# schematic_D_Amplifier_1.net
KiCad netlist of a schematic drawn in EAGLE
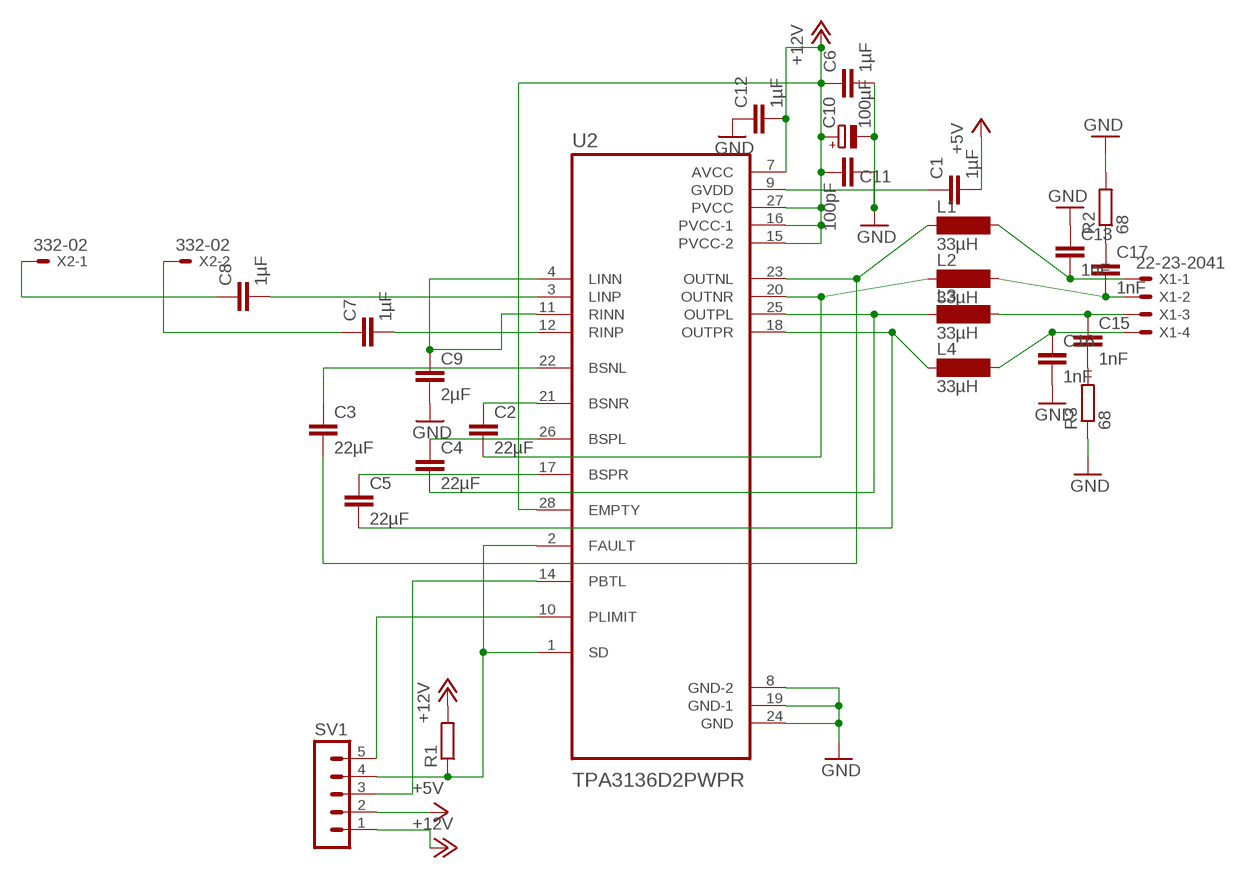
[diagram p0: schematic, sheet 1]

(export (version "E")
  (design (tool "Eeschema 10.0.6"))
  (components
    (comp (ref "C1")
      (value "1µF")
      (footprint "eagle-import:C025-025X050")
      (libsource (lib "eagle-import") (part "C-EU025-025X050"))
    )
    (comp (ref "C2")
      (value "22µF")
      (footprint "eagle-import:C025-025X050")
      (libsource (lib "eagle-import") (part "C-EU025-025X050"))
    )
    (comp (ref "C3")
      (value "22µF")
      (footprint "eagle-import:C025-025X050")
      (libsource (lib "eagle-import") (part "C-EU025-025X050"))
    )
    (comp (ref "C4")
      (value "22µF")
      (footprint "eagle-import:C025-025X050")
      (libsource (lib "eagle-import") (part "C-EU025-025X050"))
    )
    (comp (ref "C5")
      (value "22µF")
      (footprint "eagle-import:C025-025X050")
      (libsource (lib "eagle-import") (part "C-EU025-025X050"))
    )
    (comp (ref "C6")
      (value "1µF")
      (footprint "eagle-import:C025-025X050")
      (libsource (lib "eagle-import") (part "C-EU025-025X050"))
    )
    (comp (ref "C7")
      (value "1µF")
      (footprint "eagle-import:C025-025X050")
      (libsource (lib "eagle-import") (part "C-EU025-025X050"))
    )
    (comp (ref "C8")
      (value "1µF")
      (footprint "eagle-import:C025-025X050")
      (libsource (lib "eagle-import") (part "C-EU025-025X050"))
    )
    (comp (ref "C9")
      (value "2µF")
      (footprint "eagle-import:C025-025X050")
      (libsource (lib "eagle-import") (part "C-EU025-025X050"))
    )
    (comp (ref "C10")
      (value "100µF")
      (footprint "eagle-import:140CLH-1010")
      (libsource (lib "eagle-import") (part "CPOL-EU140CLH-1010"))
    )
    (comp (ref "C11")
      (value "100pF")
      (footprint "eagle-import:C025-025X050")
      (libsource (lib "eagle-import") (part "C-EU025-025X050"))
    )
    (comp (ref "C12")
      (value "1µF")
      (footprint "eagle-import:C025-025X050")
      (libsource (lib "eagle-import") (part "C-EU025-025X050"))
    )
    (comp (ref "C13")
      (value "1nF")
      (footprint "eagle-import:C025-025X050")
      (libsource (lib "eagle-import") (part "C-EU025-025X050"))
    )
    (comp (ref "C15")
      (value "1nF")
      (footprint "eagle-import:C025-025X050")
      (libsource (lib "eagle-import") (part "C-EU025-025X050"))
    )
    (comp (ref "C16")
      (value "1nF")
      (footprint "eagle-import:C025-025X050")
      (libsource (lib "eagle-import") (part "C-EU025-025X050"))
    )
    (comp (ref "C17")
      (value "1nF")
      (footprint "eagle-import:C025-025X050")
      (libsource (lib "eagle-import") (part "C-EU025-025X050"))
    )
    (comp (ref "L1")
      (value "33µH")
      (footprint "eagle-import:SD12-680")
      (fields (field (name "MF") "BUSSMANN") (field (name "MPN") "SD12-680"))
      (libsource (lib "eagle-import") (part "SD12-680"))
    )
    (comp (ref "L2")
      (value "33µH")
      (footprint "eagle-import:SD12-680")
      (fields (field (name "MF") "BUSSMANN") (field (name "MPN") "SD12-680"))
      (libsource (lib "eagle-import") (part "SD12-680"))
    )
    (comp (ref "L3")
      (value "33µH")
      (footprint "eagle-import:SD12-680")
      (fields (field (name "MF") "BUSSMANN") (field (name "MPN") "SD12-680"))
      (libsource (lib "eagle-import") (part "SD12-680"))
    )
    (comp (ref "L4")
      (value "33µH")
      (footprint "eagle-import:SD12-680")
      (fields (field (name "MF") "BUSSMANN") (field (name "MPN") "SD12-680"))
      (libsource (lib "eagle-import") (part "SD12-680"))
    )
    (comp (ref "R1")
      (value "R-EU_0204/7")
      (footprint "eagle-import:0204_7")
      (libsource (lib "eagle-import") (part "R-EU_0204/7"))
    )
    (comp (ref "R2")
      (value "68")
      (footprint "eagle-import:0204_7")
      (libsource (lib "eagle-import") (part "R-EU_0204/7"))
    )
    (comp (ref "R3")
      (value "68")
      (footprint "eagle-import:0204_7")
      (libsource (lib "eagle-import") (part "R-EU_0204/7"))
    )
    (comp (ref "SV1")
      (value "MA05-1")
      (footprint "eagle-import:MA05-1")
      (libsource (lib "eagle-import") (part "MA05-1"))
    )
    (comp (ref "U2")
      (value "TPA3136D2PWPR")
      (footprint "eagle-import:IC_TPS61196PWPRQ1")
      (fields (field (name "MF") "Texas Instruments"))
      (libsource (lib "eagle-import") (part "TPA3136D2PWPR"))
    )
    (comp (ref "X1")
      (value "22-23-2041")
      (footprint "eagle-import:22-23-2041")
      (fields (field (name "MF") "MOLEX"))
      (libsource (lib "eagle-import") (part "22-23-2041"))
    )
    (comp (ref "X2")
      (value "332-02")
      (footprint "eagle-import:332-02")
      (libsource (lib "eagle-import") (part "332-02"))
    )
  )
  (nets
    (net (code "1") (name "+5V") (class "Default")
      (node (ref "C1") (pin "2") (pinfunction "2_2") (pintype "passive"))
      (node (ref "SV1") (pin "2") (pinfunction "2_2") (pintype "passive"))
    )
    (net (code "2") (name "+12V") (class "Default")
      (node (ref "C10") (pin "+") (pinfunction "+_+") (pintype "passive"))
      (node (ref "C11") (pin "2") (pinfunction "2_2") (pintype "passive"))
      (node (ref "C12") (pin "2") (pinfunction "2_2") (pintype "passive"))
      (node (ref "C6") (pin "1") (pinfunction "1_1") (pintype "passive"))
      (node (ref "R1") (pin "2") (pinfunction "2_2") (pintype "passive"))
      (node (ref "SV1") (pin "1") (pinfunction "1_1") (pintype "passive"))
      (node (ref "U2") (pin "15") (pinfunction "PVCC-2_15") (pintype "power_in"))
      (node (ref "U2") (pin "16") (pinfunction "PVCC-1_16") (pintype "power_in"))
      (node (ref "U2") (pin "27") (pinfunction "PVCC_27") (pintype "power_in"))
      (node (ref "U2") (pin "28") (pinfunction "EMPTY_28") (pintype "bidirectional"))
      (node (ref "U2") (pin "7") (pinfunction "AVCC_7") (pintype "power_in"))
    )
    (net (code "3") (name "GND") (class "Default")
      (node (ref "C10") (pin "-") (pinfunction "-_-") (pintype "passive"))
      (node (ref "C11") (pin "1") (pinfunction "1_1") (pintype "passive"))
      (node (ref "C12") (pin "1") (pinfunction "1_1") (pintype "passive"))
      (node (ref "C13") (pin "1") (pinfunction "1_1") (pintype "passive"))
      (node (ref "C16") (pin "2") (pinfunction "2_2") (pintype "passive"))
      (node (ref "C6") (pin "2") (pinfunction "2_2") (pintype "passive"))
      (node (ref "C9") (pin "2") (pinfunction "2_2") (pintype "passive"))
      (node (ref "R2") (pin "2") (pinfunction "2_2") (pintype "passive"))
      (node (ref "R3") (pin "1") (pinfunction "1_1") (pintype "passive"))
      (node (ref "U2") (pin "19") (pinfunction "GND-1_19") (pintype "power_in"))
      (node (ref "U2") (pin "24") (pinfunction "GND_24") (pintype "power_in"))
      (node (ref "U2") (pin "8") (pinfunction "GND-2_8") (pintype "power_in"))
    )
    (net (code "4") (name "Net-(C15-Pad2)") (class "Default")
      (node (ref "C15") (pin "2") (pinfunction "2_2") (pintype "passive"))
      (node (ref "R3") (pin "2") (pinfunction "2_2") (pintype "passive"))
    )
    (net (code "5") (name "Net-(C17-Pad1)") (class "Default")
      (node (ref "C17") (pin "1") (pinfunction "1_1") (pintype "passive"))
      (node (ref "R2") (pin "1") (pinfunction "1_1") (pintype "passive"))
    )
    (net (code "6") (name "Net-(U2-BSNL)") (class "Default")
      (node (ref "C3") (pin "1") (pinfunction "1_1") (pintype "passive"))
      (node (ref "U2") (pin "22") (pinfunction "BSNL_22") (pintype "bidirectional"))
    )
    (net (code "7") (name "Net-(U2-BSNR)") (class "Default")
      (node (ref "C2") (pin "1") (pinfunction "1_1") (pintype "passive"))
      (node (ref "U2") (pin "21") (pinfunction "BSNR_21") (pintype "bidirectional"))
    )
    (net (code "8") (name "Net-(U2-BSPL)") (class "Default")
      (node (ref "C4") (pin "1") (pinfunction "1_1") (pintype "passive"))
      (node (ref "U2") (pin "26") (pinfunction "BSPL_26") (pintype "bidirectional"))
    )
    (net (code "9") (name "Net-(U2-BSPR)") (class "Default")
      (node (ref "C5") (pin "1") (pinfunction "1_1") (pintype "passive"))
      (node (ref "U2") (pin "17") (pinfunction "BSPR_17") (pintype "bidirectional"))
    )
    (net (code "10") (name "Net-(U2-FAULT)") (class "Default")
      (node (ref "R1") (pin "1") (pinfunction "1_1") (pintype "passive"))
      (node (ref "SV1") (pin "4") (pinfunction "4_4") (pintype "passive"))
      (node (ref "U2") (pin "1") (pinfunction "SD_1") (pintype "bidirectional"))
      (node (ref "U2") (pin "2") (pinfunction "FAULT_2") (pintype "bidirectional"))
    )
    (net (code "11") (name "Net-(U2-GVDD)") (class "Default")
      (node (ref "C1") (pin "1") (pinfunction "1_1") (pintype "passive"))
      (node (ref "U2") (pin "9") (pinfunction "GVDD_9") (pintype "power_in"))
    )
    (net (code "12") (name "Net-(U2-LINN)") (class "Default")
      (node (ref "C9") (pin "1") (pinfunction "1_1") (pintype "passive"))
      (node (ref "U2") (pin "11") (pinfunction "RINN_11") (pintype "input"))
      (node (ref "U2") (pin "4") (pinfunction "LINN_4") (pintype "input"))
    )
    (net (code "13") (name "Net-(U2-LINP)") (class "Default")
      (node (ref "C8") (pin "2") (pinfunction "2_2") (pintype "passive"))
      (node (ref "U2") (pin "3") (pinfunction "LINP_3") (pintype "input"))
    )
    (net (code "14") (name "Net-(U2-OUTNL)") (class "Default")
      (node (ref "C3") (pin "2") (pinfunction "2_2") (pintype "passive"))
      (node (ref "L1") (pin "1") (pinfunction "1_1") (pintype "passive"))
      (node (ref "U2") (pin "23") (pinfunction "OUTNL_23") (pintype "output"))
    )
    (net (code "15") (name "Net-(U2-OUTNR)") (class "Default")
      (node (ref "C2") (pin "2") (pinfunction "2_2") (pintype "passive"))
      (node (ref "L2") (pin "1") (pinfunction "1_1") (pintype "passive"))
      (node (ref "U2") (pin "20") (pinfunction "OUTNR_20") (pintype "output"))
    )
    (net (code "16") (name "Net-(U2-OUTPL)") (class "Default")
      (node (ref "C4") (pin "2") (pinfunction "2_2") (pintype "passive"))
      (node (ref "L3") (pin "1") (pinfunction "1_1") (pintype "passive"))
      (node (ref "U2") (pin "25") (pinfunction "OUTPL_25") (pintype "output"))
    )
    (net (code "17") (name "Net-(U2-OUTPR)") (class "Default")
      (node (ref "C5") (pin "2") (pinfunction "2_2") (pintype "passive"))
      (node (ref "L4") (pin "1") (pinfunction "1_1") (pintype "passive"))
      (node (ref "U2") (pin "18") (pinfunction "OUTPR_18") (pintype "output"))
    )
    (net (code "18") (name "Net-(U2-PBTL)") (class "Default")
      (node (ref "SV1") (pin "3") (pinfunction "3_3") (pintype "passive"))
      (node (ref "U2") (pin "14") (pinfunction "PBTL_14") (pintype "bidirectional"))
    )
    (net (code "19") (name "Net-(U2-PLIMIT)") (class "Default")
      (node (ref "SV1") (pin "5") (pinfunction "5_5") (pintype "passive"))
      (node (ref "U2") (pin "10") (pinfunction "PLIMIT_10") (pintype "bidirectional"))
    )
    (net (code "20") (name "Net-(U2-RINP)") (class "Default")
      (node (ref "C7") (pin "2") (pinfunction "2_2") (pintype "passive"))
      (node (ref "U2") (pin "12") (pinfunction "RINP_12") (pintype "input"))
    )
    (net (code "21") (name "Net-(X1A-S)") (class "Default")
      (node (ref "C13") (pin "2") (pinfunction "2_2") (pintype "passive"))
      (node (ref "L1") (pin "2") (pinfunction "2_2") (pintype "passive"))
      (node (ref "X1") (pin "1") (pinfunction "S_1") (pintype "passive"))
    )
    (net (code "22") (name "Net-(X1B-S)") (class "Default")
      (node (ref "C17") (pin "2") (pinfunction "2_2") (pintype "passive"))
      (node (ref "L2") (pin "2") (pinfunction "2_2") (pintype "passive"))
      (node (ref "X1") (pin "2") (pinfunction "S_2") (pintype "passive"))
    )
    (net (code "23") (name "Net-(X1C-S)") (class "Default")
      (node (ref "C15") (pin "1") (pinfunction "1_1") (pintype "passive"))
      (node (ref "L3") (pin "2") (pinfunction "2_2") (pintype "passive"))
      (node (ref "X1") (pin "3") (pinfunction "S_3") (pintype "passive"))
    )
    (net (code "24") (name "Net-(X1D-S)") (class "Default")
      (node (ref "C16") (pin "1") (pinfunction "1_1") (pintype "passive"))
      (node (ref "L4") (pin "2") (pinfunction "2_2") (pintype "passive"))
      (node (ref "X1") (pin "4") (pinfunction "S_4") (pintype "passive"))
    )
    (net (code "25") (name "Net-(X2A-S)") (class "Default")
      (node (ref "C8") (pin "1") (pinfunction "1_1") (pintype "passive"))
      (node (ref "X2") (pin "1") (pinfunction "S_1") (pintype "passive"))
    )
    (net (code "26") (name "Net-(X2B-S)") (class "Default")
      (node (ref "C7") (pin "1") (pinfunction "1_1") (pintype "passive"))
      (node (ref "X2") (pin "2") (pinfunction "S_2") (pintype "passive"))
    )
  )
)
